# TMC2240-3D-Printer-Driver.net
KiCad netlist of a schematic drawn in EasyEDA Pro
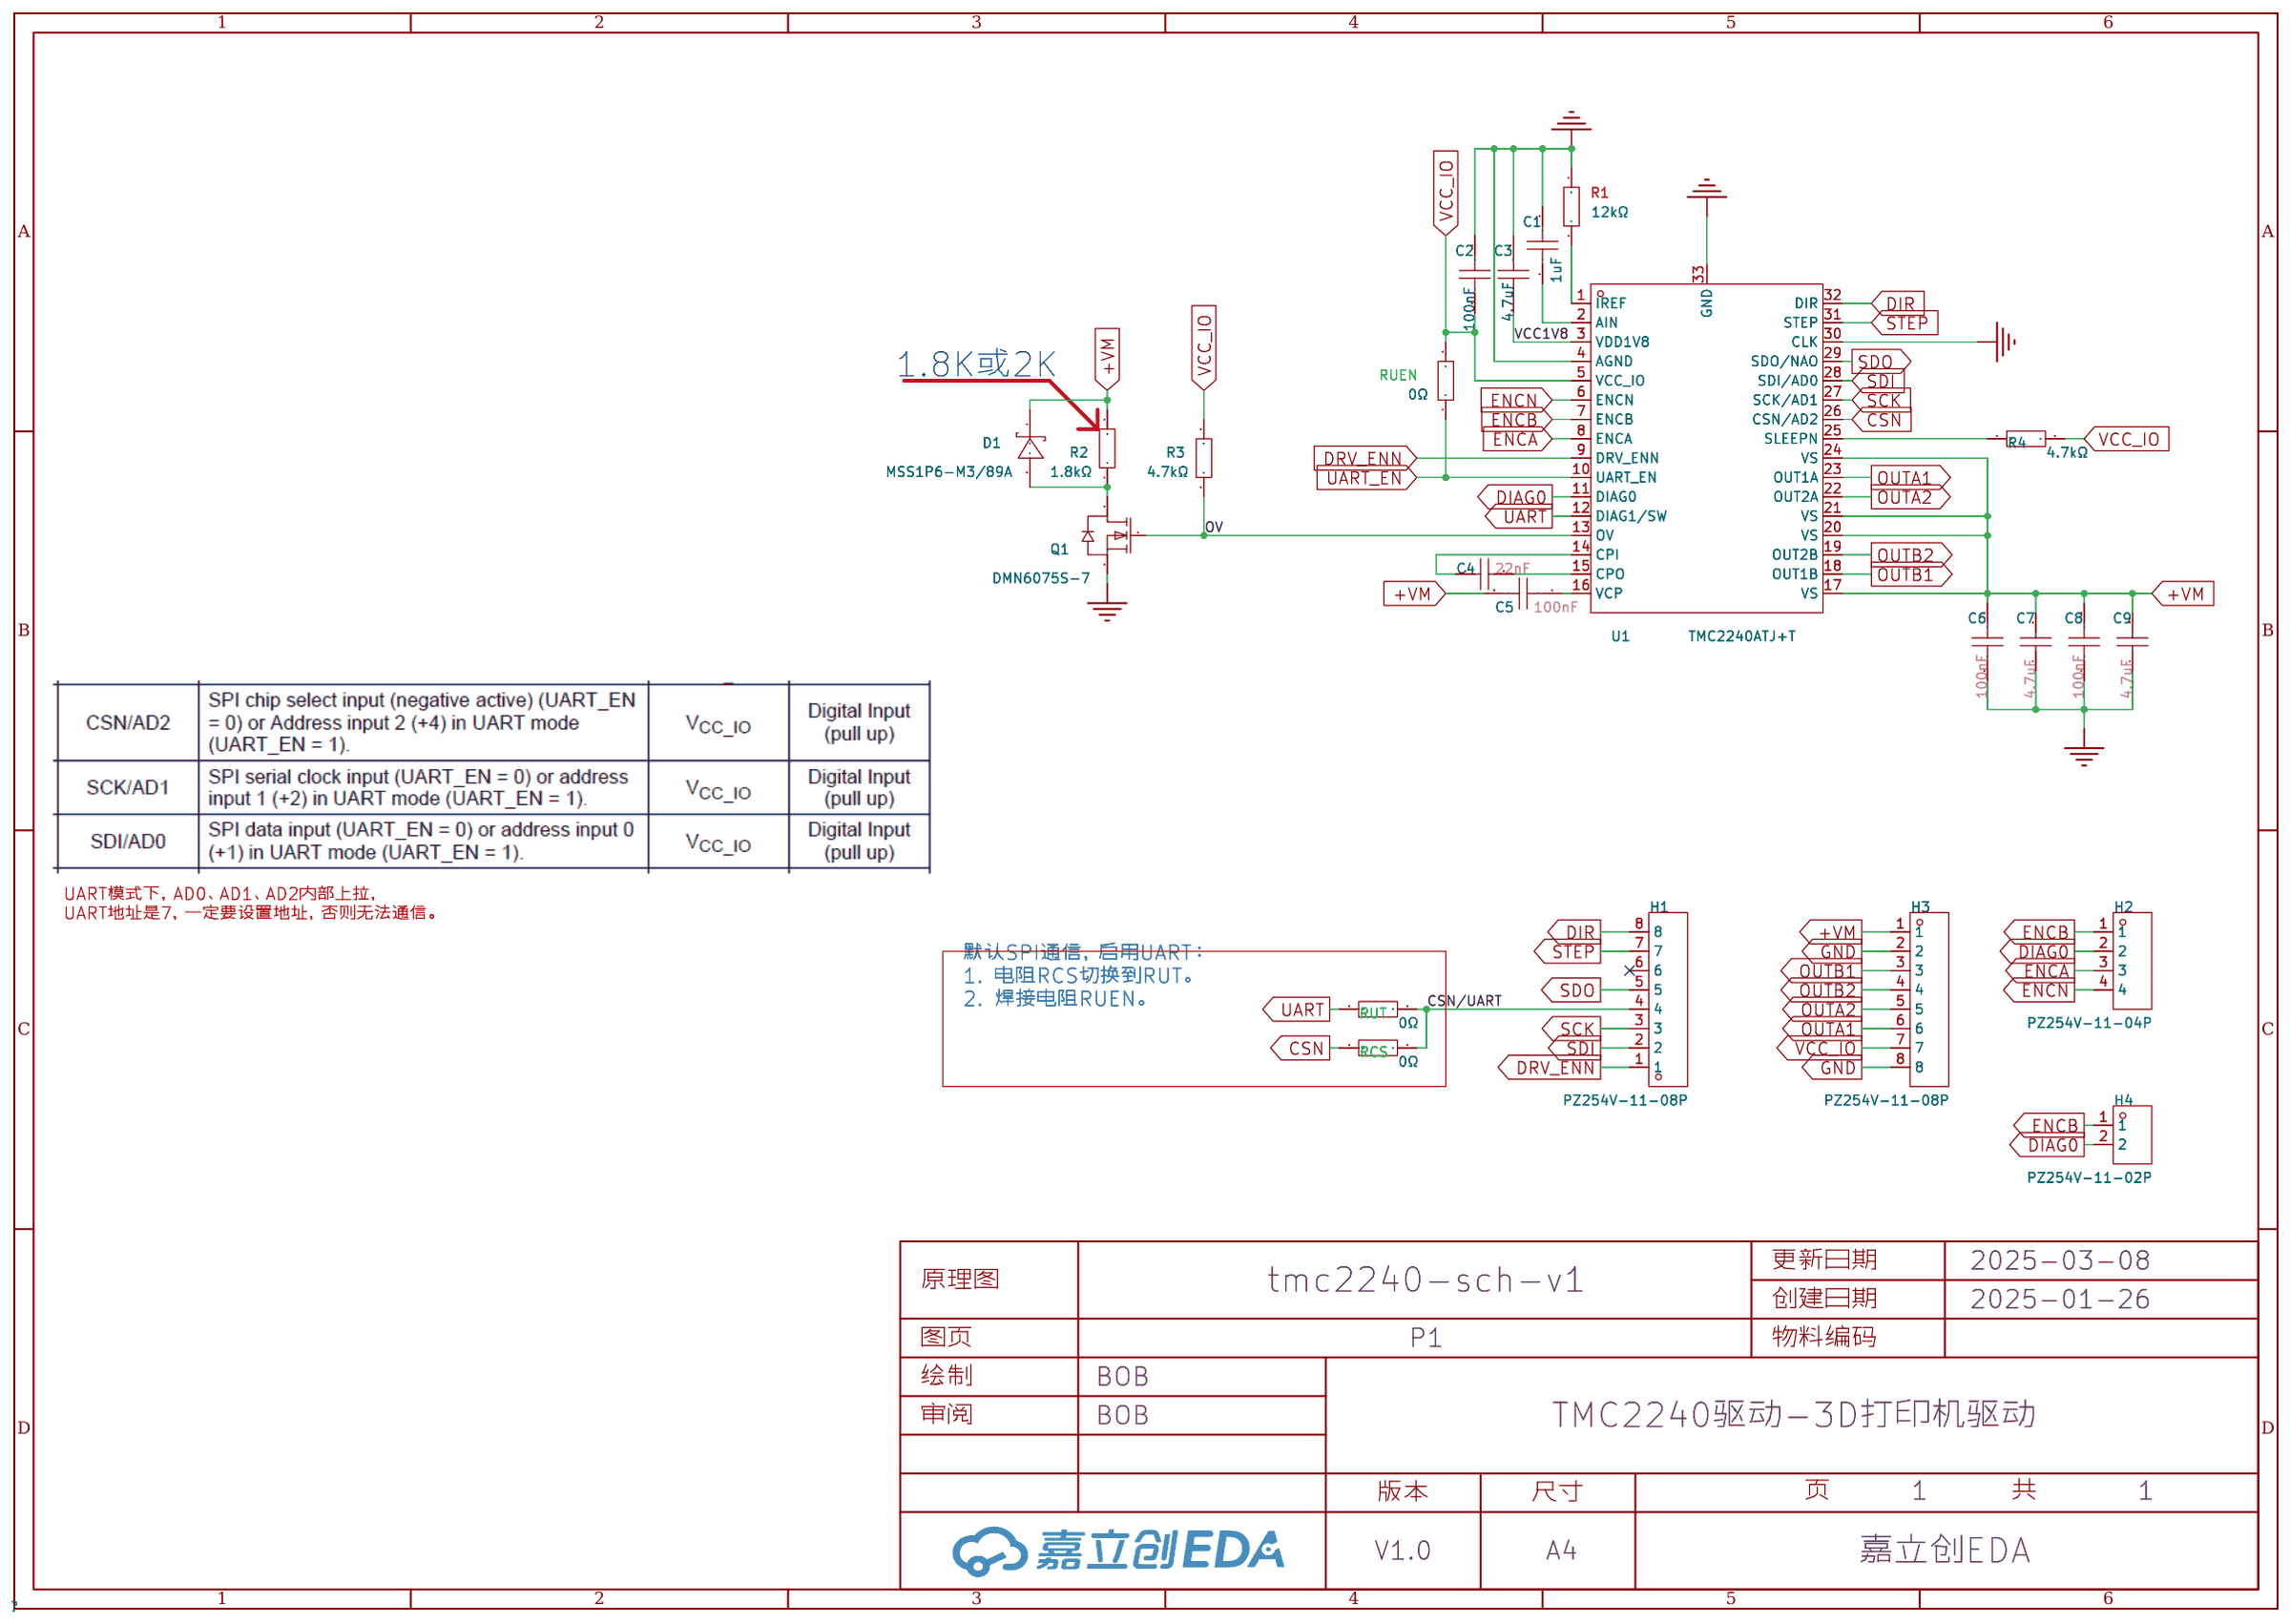
[diagram p0: schematic sheet]

(export (version "E")
  (design (tool "Eeschema 10.0.6"))
  (components
    (comp (ref "C1")
      (value "1uF")
      (footprint "easyedapro:C0402")
      (description "容值:1uF;精度:±10%;额定电压:25V;材质(温度系数):X5R;")
      (fields
        (field (name "Manufacturer Part") "CL05A105KA5NQNC")
        (field (name "Manufacturer") "SAMSUNG(三星)")
      )
      (libsource (lib "easyedapro") (part "CL05A105KA5NQNC"))
    )
    (comp (ref "C2")
      (value "100nF")
      (footprint "easyedapro:C0402")
      (description "容值:100nF;精度:±10%;额定电压:50V;材质(温度系数):X7R;")
      (fields
        (field (name "Manufacturer Part") "CL05B104KB54PNC")
        (field (name "Manufacturer") "SAMSUNG(三星)")
      )
      (libsource (lib "easyedapro") (part "CL05B104KB54PNC"))
    )
    (comp (ref "C3")
      (value "4.7uF")
      (footprint "easyedapro:C0402")
      (description "容值:4.7uF;精度:±10%;额定电压:10V;材质(温度系数):X5R;")
      (fields
        (field (name "Manufacturer Part") "CL05A475KP5NRNC")
        (field (name "Manufacturer") "SAMSUNG(三星)")
      )
      (libsource (lib "easyedapro") (part "CL05A475KP5NRNC"))
    )
    (comp (ref "C4")
      (value "22nF")
      (footprint "easyedapro:C0402")
      (description "容值:22nF;精度:±10%;额定电压:50V;材质(温度系数):X7R;")
      (fields
        (field (name "Manufacturer Part") "GRM155R71H223KA12D")
        (field (name "Manufacturer") "muRata(村田)")
      )
      (libsource (lib "easyedapro") (part "GRM155R71H223KA12D"))
    )
    (comp (ref "C5")
      (value "100nF")
      (footprint "easyedapro:C0402")
      (description "容值:100nF;精度:±10%;额定电压:50V;材质(温度系数):X7R;")
      (fields
        (field (name "Manufacturer Part") "CL05B104KB54PNC")
        (field (name "Manufacturer") "SAMSUNG(三星)")
      )
      (libsource (lib "easyedapro") (part "CL05B104KB54PNC"))
    )
    (comp (ref "C6")
      (value "100nF")
      (footprint "easyedapro:C0402")
      (description "容值:100nF;精度:±10%;额定电压:50V;材质(温度系数):X7R;")
      (fields
        (field (name "Manufacturer Part") "CL05B104KB54PNC")
        (field (name "Manufacturer") "SAMSUNG(三星)")
      )
      (libsource (lib "easyedapro") (part "CL05B104KB54PNC"))
    )
    (comp (ref "C7")
      (value "4.7uF")
      (footprint "easyedapro:C0805")
      (description "容值:4.7uF;精度:±10%;额定电压:50V;材质(温度系数):X5R;")
      (fields
        (field (name "Manufacturer Part") "CL21A475KBQNNNE")
        (field (name "Manufacturer") "SAMSUNG(三星)")
      )
      (libsource (lib "easyedapro") (part "CL21A475KBQNNNE"))
    )
    (comp (ref "C8")
      (value "100nF")
      (footprint "easyedapro:C0402")
      (description "容值:100nF;精度:±10%;额定电压:50V;材质(温度系数):X7R;")
      (fields
        (field (name "Manufacturer Part") "CL05B104KB54PNC")
        (field (name "Manufacturer") "SAMSUNG(三星)")
      )
      (libsource (lib "easyedapro") (part "CL05B104KB54PNC"))
    )
    (comp (ref "C9")
      (value "4.7uF")
      (footprint "easyedapro:C0805")
      (description "容值:4.7uF;精度:±10%;额定电压:50V;材质(温度系数):X5R;")
      (fields
        (field (name "Manufacturer Part") "CL21A475KBQNNNE")
        (field (name "Manufacturer") "SAMSUNG(三星)")
      )
      (libsource (lib "easyedapro") (part "CL21A475KBQNNNE"))
    )
    (comp (ref "D1")
      (value "MSS1P6-M3/89A")
      (footprint "easyedapro:MICROSMP_L2.2-W1.3-LS2.5-RD")
      (description "正向压降(Vf):680mV@1A;直流反向耐压(Vr):60V;平均整流电流(Io):1A;")
      (fields (field (name "Manufacturer") "VISHAY(威世)"))
      (libsource (lib "easyedapro") (part "MSS1P6-M3/89A"))
    )
    (comp (ref "H1")
      (value "PZ254V-11-08P")
      (footprint "easyedapro:HDR-TH_8P-P2.54-V-M")
      (fields (field (name "Manufacturer") "XFCN(兴飞)"))
      (libsource (lib "easyedapro") (part "PZ254V-11-08P"))
    )
    (comp (ref "H2")
      (value "PZ254V-11-04P")
      (footprint "easyedapro:HDR-TH_4P-P2.54-V-M")
      (fields (field (name "Manufacturer") "XFCN(兴飞)"))
      (libsource (lib "easyedapro") (part "PZ254V-11-04P_C2691448"))
    )
    (comp (ref "H3")
      (value "PZ254V-11-08P")
      (footprint "easyedapro:HDR-TH_8P-P2.54-V-M")
      (fields (field (name "Manufacturer") "XFCN(兴飞)"))
      (libsource (lib "easyedapro") (part "PZ254V-11-08P"))
    )
    (comp (ref "H4")
      (value "PZ254V-11-02P")
      (footprint "easyedapro:HDR-TH_2P-P2.54-V-M")
      (fields (field (name "Manufacturer") "XFCN(兴飞)"))
      (libsource (lib "easyedapro") (part "PZ254V-11-02P"))
    )
    (comp (ref "Q1")
      (value "DMN6075S-7")
      (footprint "easyedapro:SOT-23-3_L2.9-W1.3-P1.90-LS2.4-BR")
      (fields (field (name "Manufacturer") "DIODES(美台)"))
      (libsource (lib "easyedapro") (part "DMN6075S-7"))
    )
    (comp (ref "R1")
      (value "12kΩ")
      (footprint "easyedapro:R0603")
      (description "电阻类型:厚膜电阻;阻值:12kΩ;精度:±1%;功率:100mW;最大工作电压:75V;温度系数:±100ppm/°C;")
      (fields
        (field (name "Manufacturer Part") "0603WAF1202T5E")
        (field (name "Manufacturer") "UNI-ROYAL(厚声)")
      )
      (libsource (lib "easyedapro") (part "0603WAF1202T5E"))
    )
    (comp (ref "R2")
      (value "1.8kΩ")
      (footprint "easyedapro:R2512")
      (description "电阻类型:厚膜电阻;阻值:1.8kΩ;精度:±5%;功率:1W;最大工作电压:200V;温度系数:±100ppm/°C;")
      (fields (field (name "Manufacturer Part") "RC2512JK-071K8L") (field (name "Manufacturer") "YAGEO(国巨)"))
      (libsource (lib "easyedapro") (part "RC2512JK-071K8L"))
    )
    (comp (ref "R3")
      (value "4.7kΩ")
      (footprint "easyedapro:R0402")
      (description "电阻类型:厚膜电阻;阻值:4.7kΩ;精度:±1%;功率:62.5mW;最大工作电压:50V;温度系数:±100ppm/°C;")
      (fields
        (field (name "Manufacturer Part") "0402WGF4701TCE")
        (field (name "Manufacturer") "UNI-ROYAL(厚声)")
      )
      (libsource (lib "easyedapro") (part "0402WGF4701TCE"))
    )
    (comp (ref "R4")
      (value "4.7kΩ")
      (footprint "easyedapro:R0402")
      (description "电阻类型:厚膜电阻;阻值:4.7kΩ;精度:±1%;功率:62.5mW;最大工作电压:50V;温度系数:±100ppm/°C;")
      (fields
        (field (name "Manufacturer Part") "0402WGF4701TCE")
        (field (name "Manufacturer") "UNI-ROYAL(厚声)")
      )
      (libsource (lib "easyedapro") (part "0402WGF4701TCE"))
    )
    (comp (ref "RCS")
      (value "0Ω")
      (footprint "easyedapro:R0402")
      (description "电阻类型:厚膜电阻;阻值:0Ω;精度:±1%;功率:62.5mW;最大工作电压:50V;温度系数:±800ppm/°C;")
      (fields
        (field (name "Manufacturer Part") "0402WGF0000TCE")
        (field (name "Manufacturer") "UNI-ROYAL(厚声)")
      )
      (libsource (lib "easyedapro") (part "0402WGF0000TCE"))
    )
    (comp (ref "RUEN")
      (value "0Ω")
      (footprint "easyedapro:R0402")
      (description "电阻类型:厚膜电阻;阻值:0Ω;精度:±1%;功率:62.5mW;最大工作电压:50V;温度系数:±800ppm/°C;")
      (fields
        (field (name "Manufacturer Part") "0402WGF0000TCE")
        (field (name "Manufacturer") "UNI-ROYAL(厚声)")
      )
      (libsource (lib "easyedapro") (part "0402WGF0000TCE"))
    )
    (comp (ref "RUT")
      (value "0Ω")
      (footprint "easyedapro:R0402")
      (description "电阻类型:厚膜电阻;阻值:0Ω;精度:±1%;功率:62.5mW;最大工作电压:50V;温度系数:±800ppm/°C;")
      (fields
        (field (name "Manufacturer Part") "0402WGF0000TCE")
        (field (name "Manufacturer") "UNI-ROYAL(厚声)")
      )
      (libsource (lib "easyedapro") (part "0402WGF0000TCE"))
    )
    (comp (ref "U1")
      (value "TMC2240ATJ+T")
      (footprint "easyedapro:TQFN-32_L5.0-W5.0-P0.50-BL-EP3.5")
      (fields (field (name "Manufacturer") "TRINAMIC"))
      (libsource (lib "easyedapro") (part "TMC2240ATJ+T"))
    )
  )
  (nets
    (net (code "1") (name "+VM") (class "Default")
      (node (ref "C5") (pin "2") (pinfunction "2_2") (pintype "unspecified"))
      (node (ref "C6") (pin "2") (pinfunction "2_2") (pintype "unspecified"))
      (node (ref "C7") (pin "2") (pinfunction "2_2") (pintype "input"))
      (node (ref "C8") (pin "2") (pinfunction "2_2") (pintype "unspecified"))
      (node (ref "C9") (pin "2") (pinfunction "2_2") (pintype "input"))
      (node (ref "D1") (pin "1") (pinfunction "A_1") (pintype "unspecified"))
      (node (ref "H3") (pin "1") (pinfunction "1_1") (pintype "unspecified"))
      (node (ref "R2") (pin "2") (pinfunction "2_2") (pintype "input"))
      (node (ref "U1") (pin "17") (pinfunction "VS_17") (pintype "unspecified"))
      (node (ref "U1") (pin "20") (pinfunction "VS_20") (pintype "unspecified"))
      (node (ref "U1") (pin "21") (pinfunction "VS_21") (pintype "unspecified"))
      (node (ref "U1") (pin "24") (pinfunction "VS_24") (pintype "unspecified"))
    )
    (net (code "2") (name "/CSN{slash}UART") (class "Default")
      (node (ref "H1") (pin "4") (pinfunction "4_4") (pintype "unspecified"))
      (node (ref "RCS") (pin "2") (pinfunction "2_2") (pintype "input"))
      (node (ref "RUT") (pin "2") (pinfunction "2_2") (pintype "input"))
    )
    (net (code "3") (name "/OV") (class "Default")
      (node (ref "Q1") (pin "1") (pinfunction "G_1") (pintype "unspecified"))
      (node (ref "R3") (pin "2") (pinfunction "2_2") (pintype "input"))
      (node (ref "U1") (pin "13") (pinfunction "OV_13") (pintype "unspecified"))
    )
    (net (code "4") (name "/VCC1V8") (class "Default")
      (node (ref "C3") (pin "1") (pinfunction "1_1") (pintype "unspecified"))
      (node (ref "U1") (pin "3") (pinfunction "VDD1V8_3") (pintype "unspecified"))
    )
    (net (code "5") (name "CSN") (class "Default")
      (node (ref "RCS") (pin "1") (pinfunction "1_1") (pintype "input"))
      (node (ref "U1") (pin "26") (pinfunction "CSN/AD2_26") (pintype "unspecified"))
    )
    (net (code "6") (name "DIAG0") (class "Default")
      (node (ref "H2") (pin "2") (pinfunction "2_2") (pintype "unspecified"))
      (node (ref "H4") (pin "2") (pinfunction "2_2") (pintype "unspecified"))
      (node (ref "U1") (pin "11") (pinfunction "DIAG0_11") (pintype "unspecified"))
    )
    (net (code "7") (name "DIR") (class "Default")
      (node (ref "H1") (pin "8") (pinfunction "8_8") (pintype "unspecified"))
      (node (ref "U1") (pin "32") (pinfunction "DIR_32") (pintype "unspecified"))
    )
    (net (code "8") (name "DRV_ENN") (class "Default")
      (node (ref "H1") (pin "1") (pinfunction "1_1") (pintype "unspecified"))
      (node (ref "U1") (pin "9") (pinfunction "DRV_ENN_9") (pintype "unspecified"))
    )
    (net (code "9") (name "ENCA") (class "Default")
      (node (ref "H2") (pin "3") (pinfunction "3_3") (pintype "unspecified"))
      (node (ref "U1") (pin "8") (pinfunction "ENCA_8") (pintype "unspecified"))
    )
    (net (code "10") (name "ENCB") (class "Default")
      (node (ref "H2") (pin "1") (pinfunction "1_1") (pintype "unspecified"))
      (node (ref "H4") (pin "1") (pinfunction "1_1") (pintype "unspecified"))
      (node (ref "U1") (pin "7") (pinfunction "ENCB_7") (pintype "unspecified"))
    )
    (net (code "11") (name "ENCN") (class "Default")
      (node (ref "H2") (pin "4") (pinfunction "4_4") (pintype "unspecified"))
      (node (ref "U1") (pin "6") (pinfunction "ENCN_6") (pintype "unspecified"))
    )
    (net (code "12") (name "GND") (class "Default")
      (node (ref "C1") (pin "2") (pinfunction "2_2") (pintype "unspecified"))
      (node (ref "C2") (pin "2") (pinfunction "2_2") (pintype "unspecified"))
      (node (ref "C3") (pin "2") (pinfunction "2_2") (pintype "unspecified"))
      (node (ref "C6") (pin "1") (pinfunction "1_1") (pintype "unspecified"))
      (node (ref "C7") (pin "1") (pinfunction "1_1") (pintype "input"))
      (node (ref "C8") (pin "1") (pinfunction "1_1") (pintype "unspecified"))
      (node (ref "C9") (pin "1") (pinfunction "1_1") (pintype "input"))
      (node (ref "H3") (pin "2") (pinfunction "2_2") (pintype "unspecified"))
      (node (ref "H3") (pin "8") (pinfunction "8_8") (pintype "unspecified"))
      (node (ref "Q1") (pin "2") (pinfunction "S_2") (pintype "unspecified"))
      (node (ref "R1") (pin "2") (pinfunction "2_2") (pintype "input"))
      (node (ref "U1") (pin "30") (pinfunction "CLK_30") (pintype "unspecified"))
      (node (ref "U1") (pin "33") (pinfunction "GND_33") (pintype "unspecified"))
      (node (ref "U1") (pin "4") (pinfunction "AGND_4") (pintype "unspecified"))
    )
    (net (code "13") (name "Net-(D1-K)") (class "Default")
      (node (ref "D1") (pin "2") (pinfunction "K_2") (pintype "unspecified"))
      (node (ref "Q1") (pin "3") (pinfunction "D_3") (pintype "unspecified"))
      (node (ref "R2") (pin "1") (pinfunction "1_1") (pintype "input"))
    )
    (net (code "14") (name "Net-(U1-AIN)") (class "Default")
      (node (ref "C1") (pin "1") (pinfunction "1_1") (pintype "unspecified"))
      (node (ref "U1") (pin "2") (pinfunction "AIN_2") (pintype "unspecified"))
    )
    (net (code "15") (name "Net-(U1-CPI)") (class "Default")
      (node (ref "C4") (pin "1") (pinfunction "1_1") (pintype "input"))
      (node (ref "U1") (pin "14") (pinfunction "CPI_14") (pintype "unspecified"))
    )
    (net (code "16") (name "Net-(U1-CPO)") (class "Default")
      (node (ref "C4") (pin "2") (pinfunction "2_2") (pintype "input"))
      (node (ref "U1") (pin "15") (pinfunction "CPO_15") (pintype "unspecified"))
    )
    (net (code "17") (name "Net-(U1-IREF)") (class "Default")
      (node (ref "R1") (pin "1") (pinfunction "1_1") (pintype "input"))
      (node (ref "U1") (pin "1") (pinfunction "IREF_1") (pintype "unspecified"))
    )
    (net (code "18") (name "Net-(U1-SLEEPN)") (class "Default")
      (node (ref "R4") (pin "1") (pinfunction "1_1") (pintype "input"))
      (node (ref "U1") (pin "25") (pinfunction "SLEEPN_25") (pintype "unspecified"))
    )
    (net (code "19") (name "Net-(U1-VCP)") (class "Default")
      (node (ref "C5") (pin "1") (pinfunction "1_1") (pintype "unspecified"))
      (node (ref "U1") (pin "16") (pinfunction "VCP_16") (pintype "unspecified"))
    )
    (net (code "20") (name "OUTA1") (class "Default")
      (node (ref "H3") (pin "6") (pinfunction "6_6") (pintype "unspecified"))
      (node (ref "U1") (pin "23") (pinfunction "OUT1A_23") (pintype "unspecified"))
    )
    (net (code "21") (name "OUTA2") (class "Default")
      (node (ref "H3") (pin "5") (pinfunction "5_5") (pintype "unspecified"))
      (node (ref "U1") (pin "22") (pinfunction "OUT2A_22") (pintype "unspecified"))
    )
    (net (code "22") (name "OUTB1") (class "Default")
      (node (ref "H3") (pin "3") (pinfunction "3_3") (pintype "unspecified"))
      (node (ref "U1") (pin "18") (pinfunction "OUT1B_18") (pintype "unspecified"))
    )
    (net (code "23") (name "OUTB2") (class "Default")
      (node (ref "H3") (pin "4") (pinfunction "4_4") (pintype "unspecified"))
      (node (ref "U1") (pin "19") (pinfunction "OUT2B_19") (pintype "unspecified"))
    )
    (net (code "24") (name "SCK") (class "Default")
      (node (ref "H1") (pin "3") (pinfunction "3_3") (pintype "unspecified"))
      (node (ref "U1") (pin "27") (pinfunction "SCK/AD1_27") (pintype "unspecified"))
    )
    (net (code "25") (name "SDI") (class "Default")
      (node (ref "H1") (pin "2") (pinfunction "2_2") (pintype "unspecified"))
      (node (ref "U1") (pin "28") (pinfunction "SDI/AD0_28") (pintype "unspecified"))
    )
    (net (code "26") (name "SDO") (class "Default")
      (node (ref "H1") (pin "5") (pinfunction "5_5") (pintype "unspecified"))
      (node (ref "U1") (pin "29") (pinfunction "SDO/NAO_29") (pintype "unspecified"))
    )
    (net (code "27") (name "STEP") (class "Default")
      (node (ref "H1") (pin "7") (pinfunction "7_7") (pintype "unspecified"))
      (node (ref "U1") (pin "31") (pinfunction "STEP_31") (pintype "unspecified"))
    )
    (net (code "28") (name "UART") (class "Default")
      (node (ref "RUT") (pin "1") (pinfunction "1_1") (pintype "input"))
      (node (ref "U1") (pin "12") (pinfunction "DIAG1/SW_12") (pintype "unspecified"))
    )
    (net (code "29") (name "UART_EN") (class "Default")
      (node (ref "RUEN") (pin "1") (pinfunction "1_1") (pintype "input"))
      (node (ref "U1") (pin "10") (pinfunction "UART_EN_10") (pintype "unspecified"))
    )
    (net (code "30") (name "VCC_IO") (class "Default")
      (node (ref "C2") (pin "1") (pinfunction "1_1") (pintype "unspecified"))
      (node (ref "H3") (pin "7") (pinfunction "7_7") (pintype "unspecified"))
      (node (ref "R3") (pin "1") (pinfunction "1_1") (pintype "input"))
      (node (ref "R4") (pin "2") (pinfunction "2_2") (pintype "input"))
      (node (ref "RUEN") (pin "2") (pinfunction "2_2") (pintype "input"))
      (node (ref "U1") (pin "5") (pinfunction "VCC_IO_5") (pintype "unspecified"))
    )
    (net (code "31") (name "unconnected-(H1-Pad6)") (class "Default")
      (node (ref "H1") (pin "6") (pinfunction "6_6") (pintype "unspecified+no_connect"))
    )
  )
)
